# LINEARDriver_Amp.net
KiCad netlist of a schematic drawn in Altium Designer
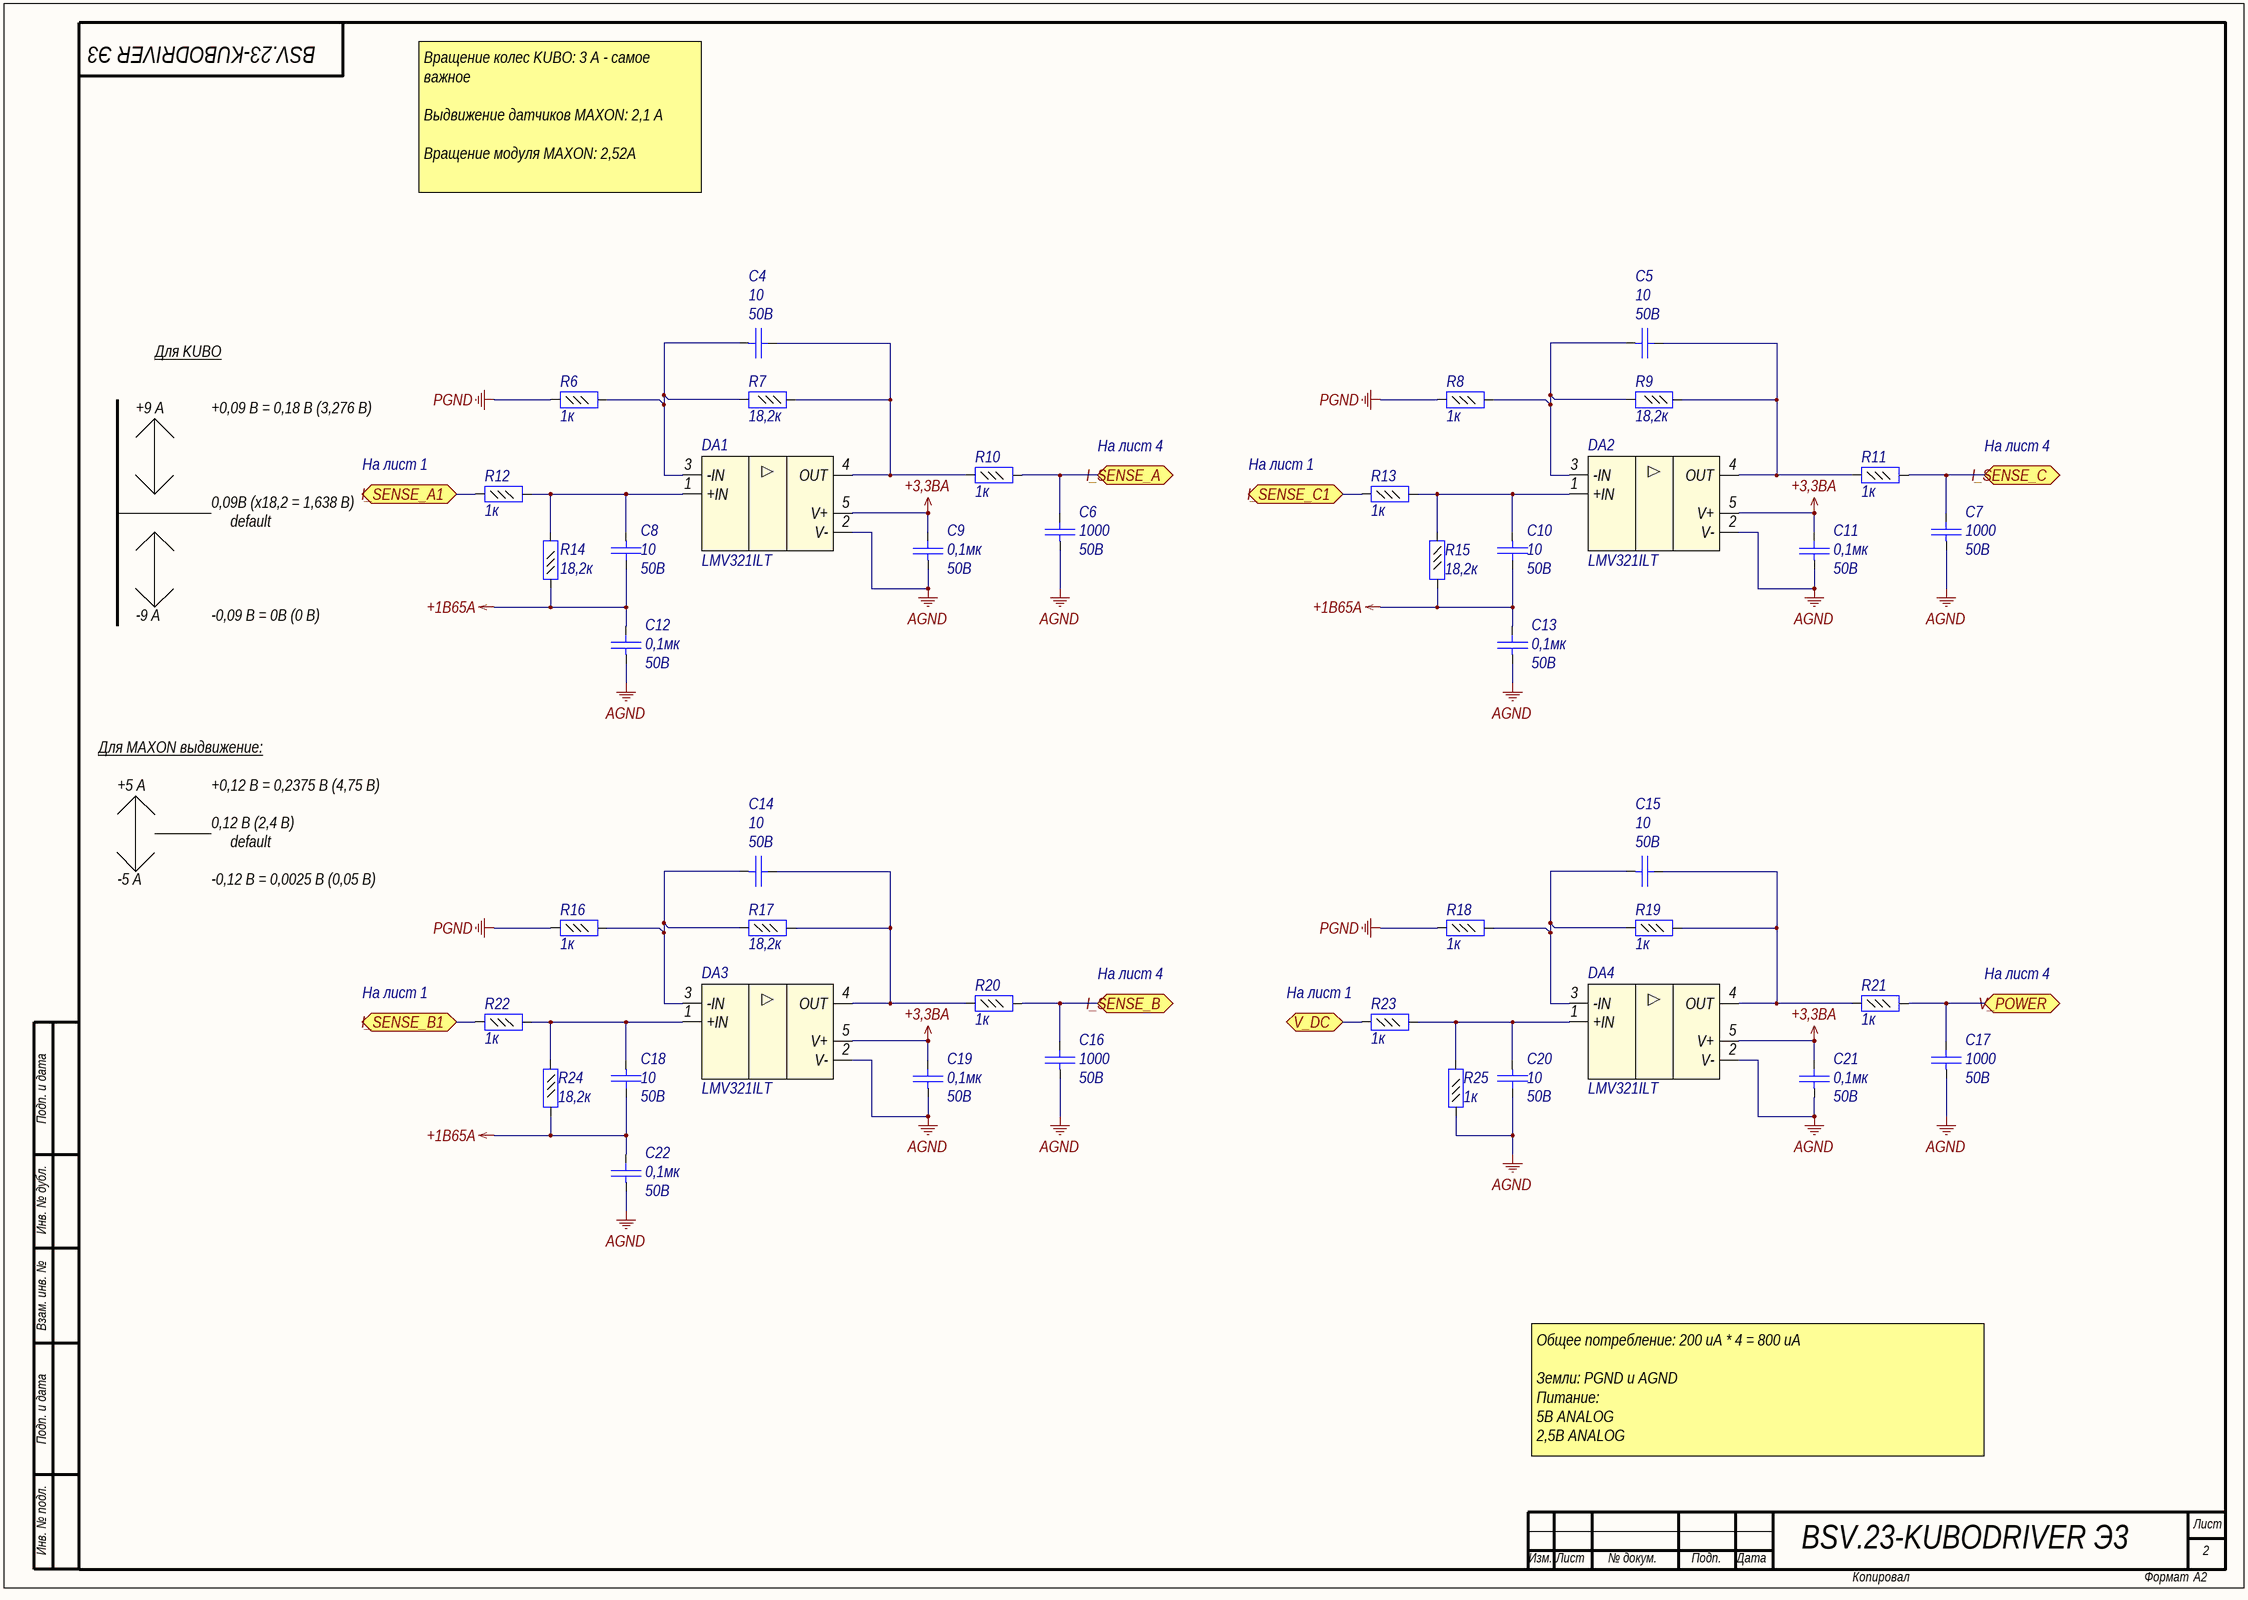
[diagram p0: LINEARDriver_Amp.SchDoc]

(export (version "E")
  (design (tool "Eeschema 10.0.6"))
  (components
    (comp (ref "C4")
      (value "10")
      (footprint "C0402")
      (description "Конденсатор")
      (fields
        (field (name "VOLTAGE") "50B")
        (field (name "PART NUMBER") "GRM1535C1H100J")
        (field (name "Comment") "Capacitor")
      )
      (libsource (lib "MOP44") (part "Capacitor"))
    )
    (comp (ref "C5")
      (value "10")
      (footprint "C0402")
      (description "Конденсатор")
      (fields
        (field (name "VOLTAGE") "50B")
        (field (name "PART NUMBER") "GRM1535C1H100J")
        (field (name "Comment") "Capacitor")
      )
      (libsource (lib "MOP44") (part "Capacitor"))
    )
    (comp (ref "C6")
      (value "1000")
      (footprint "C0402")
      (description "Конденсатор")
      (fields
        (field (name "VOLTAGE") "50B")
        (field (name "PART NUMBER") "GRM1555C1H102J")
        (field (name "Comment") "Capacitor")
      )
      (libsource (lib "MOP44") (part "Capacitor"))
    )
    (comp (ref "C7")
      (value "1000")
      (footprint "C0402")
      (description "Конденсатор")
      (fields
        (field (name "VOLTAGE") "50B")
        (field (name "PART NUMBER") "GRM1555C1H102J")
        (field (name "Comment") "Capacitor")
      )
      (libsource (lib "MOP44") (part "Capacitor"))
    )
    (comp (ref "C8")
      (value "10")
      (footprint "C0402")
      (description "Конденсатор")
      (fields
        (field (name "VOLTAGE") "50B")
        (field (name "PART NUMBER") "GRM1535C1H100J")
        (field (name "Comment") "Capacitor")
      )
      (libsource (lib "MOP44") (part "Capacitor"))
    )
    (comp (ref "C9")
      (value "0,1мк")
      (footprint "C0402")
      (description "Конденсатор")
      (fields
        (field (name "VOLTAGE") "50В")
        (field (name "PART NUMBER") "GRM155R71H104KE14D ")
        (field (name "Comment") "Capacitor")
      )
      (libsource (lib "MOP44") (part "Capacitor"))
    )
    (comp (ref "C10")
      (value "10")
      (footprint "C0402")
      (description "Конденсатор")
      (fields
        (field (name "VOLTAGE") "50B")
        (field (name "PART NUMBER") "GRM1535C1H100J")
        (field (name "Comment") "Capacitor")
      )
      (libsource (lib "MOP44") (part "Capacitor"))
    )
    (comp (ref "C11")
      (value "0,1мк")
      (footprint "C0402")
      (description "Конденсатор")
      (fields
        (field (name "VOLTAGE") "50В")
        (field (name "PART NUMBER") "GRM155R71H104KE14D ")
        (field (name "Comment") "Capacitor")
      )
      (libsource (lib "MOP44") (part "Capacitor"))
    )
    (comp (ref "C12")
      (value "0,1мк")
      (footprint "C0402")
      (description "Конденсатор")
      (fields
        (field (name "VOLTAGE") "50В")
        (field (name "PART NUMBER") "GRM155R71H104KE14D ")
        (field (name "Comment") "Capacitor")
      )
      (libsource (lib "MOP44") (part "Capacitor"))
    )
    (comp (ref "C13")
      (value "0,1мк")
      (footprint "C0402")
      (description "Конденсатор")
      (fields
        (field (name "VOLTAGE") "50В")
        (field (name "PART NUMBER") "GRM155R71H104KE14D ")
        (field (name "Comment") "Capacitor")
      )
      (libsource (lib "MOP44") (part "Capacitor"))
    )
    (comp (ref "C14")
      (value "10")
      (footprint "C0402")
      (description "Конденсатор")
      (fields
        (field (name "VOLTAGE") "50B")
        (field (name "PART NUMBER") "GRM1535C1H100J")
        (field (name "Comment") "Capacitor")
      )
      (libsource (lib "MOP44") (part "Capacitor"))
    )
    (comp (ref "C15")
      (value "10")
      (footprint "C0402")
      (description "Конденсатор")
      (fields
        (field (name "VOLTAGE") "50B")
        (field (name "PART NUMBER") "GRM1535C1H100J")
        (field (name "Comment") "Capacitor")
      )
      (libsource (lib "MOP44") (part "Capacitor"))
    )
    (comp (ref "C16")
      (value "1000")
      (footprint "C0402")
      (description "Конденсатор")
      (fields
        (field (name "VOLTAGE") "50B")
        (field (name "PART NUMBER") "GRM1555C1H102J")
        (field (name "Comment") "Capacitor")
      )
      (libsource (lib "MOP44") (part "Capacitor"))
    )
    (comp (ref "C17")
      (value "1000")
      (footprint "C0402")
      (description "Конденсатор")
      (fields
        (field (name "VOLTAGE") "50B")
        (field (name "PART NUMBER") "GRM1555C1H102J")
        (field (name "Comment") "Capacitor")
      )
      (libsource (lib "MOP44") (part "Capacitor"))
    )
    (comp (ref "C18")
      (value "10")
      (footprint "C0402")
      (description "Конденсатор")
      (fields
        (field (name "VOLTAGE") "50B")
        (field (name "PART NUMBER") "GRM1535C1H100J")
        (field (name "Comment") "Capacitor")
      )
      (libsource (lib "MOP44") (part "Capacitor"))
    )
    (comp (ref "C19")
      (value "0,1мк")
      (footprint "C0402")
      (description "Конденсатор")
      (fields
        (field (name "VOLTAGE") "50В")
        (field (name "PART NUMBER") "GRM155R71H104KE14D ")
        (field (name "Comment") "Capacitor")
      )
      (libsource (lib "MOP44") (part "Capacitor"))
    )
    (comp (ref "C20")
      (value "10")
      (footprint "C0402")
      (description "Конденсатор")
      (fields
        (field (name "VOLTAGE") "50B")
        (field (name "PART NUMBER") "GRM1535C1H100J")
        (field (name "Comment") "Capacitor")
      )
      (libsource (lib "MOP44") (part "Capacitor"))
    )
    (comp (ref "C21")
      (value "0,1мк")
      (footprint "C0402")
      (description "Конденсатор")
      (fields
        (field (name "VOLTAGE") "50В")
        (field (name "PART NUMBER") "GRM155R71H104KE14D ")
        (field (name "Comment") "Capacitor")
      )
      (libsource (lib "MOP44") (part "Capacitor"))
    )
    (comp (ref "C22")
      (value "0,1мк")
      (footprint "C0402")
      (description "Конденсатор")
      (fields
        (field (name "VOLTAGE") "50В")
        (field (name "PART NUMBER") "GRM155R71H104KE14D ")
        (field (name "Comment") "Capacitor")
      )
      (libsource (lib "MOP44") (part "Capacitor"))
    )
    (comp (ref "DA1")
      (value "LMV321ILT")
      (footprint "SOT23-5")
      (description "HIGH-DRIVE OPERATIONAL AMPLIFIERS WITH SHUTDOWN")
      (libsource (lib "MOP44") (part "LMV321ILT"))
    )
    (comp (ref "DA2")
      (value "LMV321ILT")
      (footprint "SOT23-5")
      (description "HIGH-DRIVE OPERATIONAL AMPLIFIERS WITH SHUTDOWN")
      (libsource (lib "MOP44") (part "LMV321ILT"))
    )
    (comp (ref "DA3")
      (value "LMV321ILT")
      (footprint "SOT23-5")
      (description "HIGH-DRIVE OPERATIONAL AMPLIFIERS WITH SHUTDOWN")
      (libsource (lib "MOP44") (part "LMV321ILT"))
    )
    (comp (ref "DA4")
      (value "LMV321ILT")
      (footprint "SOT23-5")
      (description "HIGH-DRIVE OPERATIONAL AMPLIFIERS WITH SHUTDOWN")
      (libsource (lib "MOP44") (part "LMV321ILT"))
    )
    (comp (ref "R6")
      (value "1к")
      (footprint "R0402")
      (description "Резистор")
      (fields (field (name "PART NUMBER") "RC0402FR-071KL") (field (name "POWER") "0,062Вт"))
      (libsource (lib "MOP44") (part "Resistor_0,062Вт"))
    )
    (comp (ref "R7")
      (value "18,2к")
      (footprint "R0402")
      (description "Резистор")
      (fields (field (name "PART NUMBER") "RC0402FR-0718K2L") (field (name "POWER") "0,062Вт"))
      (libsource (lib "") (part "Resistor_0,062Вт_2"))
    )
    (comp (ref "R8")
      (value "1к")
      (footprint "R0402")
      (description "Резистор")
      (fields (field (name "PART NUMBER") "RC0402FR-071KL") (field (name "POWER") "0,062Вт"))
      (libsource (lib "MOP44") (part "Resistor_0,062Вт"))
    )
    (comp (ref "R9")
      (value "18,2к")
      (footprint "R0402")
      (description "Резистор")
      (fields (field (name "PART NUMBER") "RC0402FR-0718K2L") (field (name "POWER") "0,062Вт"))
      (libsource (lib "") (part "Resistor_0,062Вт_2"))
    )
    (comp (ref "R10")
      (value "1к")
      (footprint "R0402")
      (description "Резистор")
      (fields (field (name "PART NUMBER") "RC0402FR-071KL") (field (name "POWER") "0,062Вт"))
      (libsource (lib "MOP44") (part "Resistor_0,062Вт"))
    )
    (comp (ref "R11")
      (value "1к")
      (footprint "R0402")
      (description "Резистор")
      (fields (field (name "PART NUMBER") "RC0402FR-071KL") (field (name "POWER") "0,062Вт"))
      (libsource (lib "MOP44") (part "Resistor_0,062Вт"))
    )
    (comp (ref "R12")
      (value "1к")
      (footprint "R0402")
      (description "Резистор")
      (fields (field (name "PART NUMBER") "RC0402FR-071KL") (field (name "POWER") "0,062Вт"))
      (libsource (lib "MOP44") (part "Resistor_0,062Вт"))
    )
    (comp (ref "R13")
      (value "1к")
      (footprint "R0402")
      (description "Резистор")
      (fields (field (name "PART NUMBER") "RC0402FR-071KL") (field (name "POWER") "0,062Вт"))
      (libsource (lib "MOP44") (part "Resistor_0,062Вт"))
    )
    (comp (ref "R14")
      (value "18,2к")
      (footprint "R0402")
      (description "Резистор")
      (fields (field (name "PART NUMBER") "RC0402FR-0718K2L") (field (name "POWER") "0,062Вт"))
      (libsource (lib "") (part "Resistor_0,062Вт_1"))
    )
    (comp (ref "R15")
      (value "18,2к")
      (footprint "R0402")
      (description "Резистор")
      (fields (field (name "PART NUMBER") "RC0402FR-0718K2L") (field (name "POWER") "0,062Вт"))
      (libsource (lib "") (part "Resistor_0,062Вт_3"))
    )
    (comp (ref "R16")
      (value "1к")
      (footprint "R0402")
      (description "Резистор")
      (fields (field (name "PART NUMBER") "RC0402FR-071KL") (field (name "POWER") "0,062Вт"))
      (libsource (lib "MOP44") (part "Resistor_0,062Вт"))
    )
    (comp (ref "R17")
      (value "18,2к")
      (footprint "R0402")
      (description "Резистор")
      (fields (field (name "PART NUMBER") "RC0402FR-0718K2L") (field (name "POWER") "0,062Вт"))
      (libsource (lib "MOP44") (part "Resistor_0,062Вт"))
    )
    (comp (ref "R18")
      (value "1к")
      (footprint "R0402")
      (description "Резистор")
      (fields (field (name "PART NUMBER") "RC0402FR-071KL") (field (name "POWER") "0,062Вт"))
      (libsource (lib "MOP44") (part "Resistor_0,062Вт"))
    )
    (comp (ref "R19")
      (value "1к")
      (footprint "R0402")
      (description "Резистор")
      (fields (field (name "PART NUMBER") "RC0402FR-071KL") (field (name "POWER") "0,062Вт"))
      (libsource (lib "MOP44") (part "Resistor_0,062Вт"))
    )
    (comp (ref "R20")
      (value "1к")
      (footprint "R0402")
      (description "Резистор")
      (fields (field (name "PART NUMBER") "RC0402FR-071KL") (field (name "POWER") "0,062Вт"))
      (libsource (lib "MOP44") (part "Resistor_0,062Вт"))
    )
    (comp (ref "R21")
      (value "1к")
      (footprint "R0402")
      (description "Резистор")
      (fields (field (name "PART NUMBER") "RC0402FR-071KL") (field (name "POWER") "0,062Вт"))
      (libsource (lib "MOP44") (part "Resistor_0,062Вт"))
    )
    (comp (ref "R22")
      (value "1к")
      (footprint "R0402")
      (description "Резистор")
      (fields (field (name "PART NUMBER") "RC0402FR-071KL") (field (name "POWER") "0,062Вт"))
      (libsource (lib "MOP44") (part "Resistor_0,062Вт"))
    )
    (comp (ref "R23")
      (value "1к")
      (footprint "R0402")
      (description "Резистор")
      (fields (field (name "PART NUMBER") "RC0402FR-071KL") (field (name "POWER") "0,062Вт"))
      (libsource (lib "MOP44") (part "Resistor_0,062Вт"))
    )
    (comp (ref "R24")
      (value "18,2к")
      (footprint "R0402")
      (description "Резистор")
      (fields (field (name "PART NUMBER") "RC0402FR-0718K2L") (field (name "POWER") "0,062Вт"))
      (libsource (lib "") (part "Resistor_0,062Вт_3"))
    )
    (comp (ref "R25")
      (value "1к")
      (footprint "R0402")
      (description "Резистор")
      (fields (field (name "PART NUMBER") "RC0402FR-071KL") (field (name "POWER") "0,062Вт"))
      (libsource (lib "") (part "Resistor_0,062Вт_1"))
    )
  )
  (nets
    (net (code "1") (name "+1B65A") (class "Default")
      (node (ref "C10") (pin "2") (pinfunction "2_2") (pintype "passive"))
      (node (ref "C12") (pin "2") (pinfunction "2_2") (pintype "passive"))
      (node (ref "C13") (pin "2") (pinfunction "2_2") (pintype "passive"))
      (node (ref "C18") (pin "2") (pinfunction "2_2") (pintype "passive"))
      (node (ref "C22") (pin "2") (pinfunction "2_2") (pintype "passive"))
      (node (ref "C8") (pin "2") (pinfunction "2_2") (pintype "passive"))
      (node (ref "R14") (pin "1") (pinfunction "1_1") (pintype "passive"))
      (node (ref "R15") (pin "2") (pinfunction "2_2") (pintype "passive"))
      (node (ref "R24") (pin "2") (pinfunction "2_2") (pintype "passive"))
    )
    (net (code "2") (name "+3,3BA") (class "Default")
      (node (ref "C11") (pin "2") (pinfunction "2_2") (pintype "passive"))
      (node (ref "C19") (pin "2") (pinfunction "2_2") (pintype "passive"))
      (node (ref "C21") (pin "2") (pinfunction "2_2") (pintype "passive"))
      (node (ref "C9") (pin "2") (pinfunction "2_2") (pintype "passive"))
      (node (ref "DA1") (pin "5") (pinfunction "V+_5") (pintype "passive"))
      (node (ref "DA2") (pin "5") (pinfunction "V+_5") (pintype "passive"))
      (node (ref "DA3") (pin "5") (pinfunction "V+_5") (pintype "passive"))
      (node (ref "DA4") (pin "5") (pinfunction "V+_5") (pintype "passive"))
    )
    (net (code "3") (name "/I_SENSE_A") (class "Default")
      (node (ref "C6") (pin "2") (pinfunction "2_2") (pintype "passive"))
      (node (ref "R10") (pin "2") (pinfunction "2_2") (pintype "passive"))
    )
    (net (code "4") (name "/I_SENSE_A1") (class "Default")
      (node (ref "R12") (pin "1") (pinfunction "1_1") (pintype "passive"))
    )
    (net (code "5") (name "/I_SENSE_B") (class "Default")
      (node (ref "C16") (pin "2") (pinfunction "2_2") (pintype "passive"))
      (node (ref "R20") (pin "2") (pinfunction "2_2") (pintype "passive"))
    )
    (net (code "6") (name "/I_SENSE_B1") (class "Default")
      (node (ref "R22") (pin "1") (pinfunction "1_1") (pintype "passive"))
    )
    (net (code "7") (name "/I_SENSE_C") (class "Default")
      (node (ref "C7") (pin "2") (pinfunction "2_2") (pintype "passive"))
      (node (ref "R11") (pin "2") (pinfunction "2_2") (pintype "passive"))
    )
    (net (code "8") (name "/I_SENSE_C1") (class "Default")
      (node (ref "R13") (pin "1") (pinfunction "1_1") (pintype "passive"))
    )
    (net (code "9") (name "/V_DC") (class "Default")
      (node (ref "R23") (pin "1") (pinfunction "1_1") (pintype "passive"))
    )
    (net (code "10") (name "/V_POWER") (class "Default")
      (node (ref "C17") (pin "2") (pinfunction "2_2") (pintype "passive"))
      (node (ref "R21") (pin "2") (pinfunction "2_2") (pintype "passive"))
    )
    (net (code "11") (name "AGND") (class "Default")
      (node (ref "C11") (pin "1") (pinfunction "1_1") (pintype "passive"))
      (node (ref "C12") (pin "1") (pinfunction "1_1") (pintype "passive"))
      (node (ref "C13") (pin "1") (pinfunction "1_1") (pintype "passive"))
      (node (ref "C16") (pin "1") (pinfunction "1_1") (pintype "passive"))
      (node (ref "C17") (pin "1") (pinfunction "1_1") (pintype "passive"))
      (node (ref "C19") (pin "1") (pinfunction "1_1") (pintype "passive"))
      (node (ref "C20") (pin "2") (pinfunction "2_2") (pintype "passive"))
      (node (ref "C21") (pin "1") (pinfunction "1_1") (pintype "passive"))
      (node (ref "C22") (pin "1") (pinfunction "1_1") (pintype "passive"))
      (node (ref "C6") (pin "1") (pinfunction "1_1") (pintype "passive"))
      (node (ref "C7") (pin "1") (pinfunction "1_1") (pintype "passive"))
      (node (ref "C9") (pin "1") (pinfunction "1_1") (pintype "passive"))
      (node (ref "DA1") (pin "2") (pinfunction "V-_2") (pintype "passive"))
      (node (ref "DA2") (pin "2") (pinfunction "V-_2") (pintype "passive"))
      (node (ref "DA3") (pin "2") (pinfunction "V-_2") (pintype "passive"))
      (node (ref "DA4") (pin "2") (pinfunction "V-_2") (pintype "passive"))
      (node (ref "R25") (pin "1") (pinfunction "1_1") (pintype "passive"))
    )
    (net (code "12") (name "Net-(DA1-+IN)") (class "Default")
      (node (ref "C8") (pin "1") (pinfunction "1_1") (pintype "passive"))
      (node (ref "DA1") (pin "1") (pinfunction "+IN_1") (pintype "passive"))
      (node (ref "R12") (pin "2") (pinfunction "2_2") (pintype "passive"))
      (node (ref "R14") (pin "2") (pinfunction "2_2") (pintype "passive"))
    )
    (net (code "13") (name "Net-(DA1--IN)") (class "Default")
      (node (ref "C4") (pin "1") (pinfunction "1_1") (pintype "passive"))
      (node (ref "DA1") (pin "3") (pinfunction "-IN_3") (pintype "passive"))
      (node (ref "R6") (pin "2") (pinfunction "2_2") (pintype "passive"))
      (node (ref "R7") (pin "2") (pinfunction "2_2") (pintype "passive"))
    )
    (net (code "14") (name "Net-(DA1-OUT)") (class "Default")
      (node (ref "C4") (pin "2") (pinfunction "2_2") (pintype "passive"))
      (node (ref "DA1") (pin "4") (pinfunction "OUT_4") (pintype "passive"))
      (node (ref "R10") (pin "1") (pinfunction "1_1") (pintype "passive"))
      (node (ref "R7") (pin "1") (pinfunction "1_1") (pintype "passive"))
    )
    (net (code "15") (name "Net-(DA2-+IN)") (class "Default")
      (node (ref "C10") (pin "1") (pinfunction "1_1") (pintype "passive"))
      (node (ref "DA2") (pin "1") (pinfunction "+IN_1") (pintype "passive"))
      (node (ref "R13") (pin "2") (pinfunction "2_2") (pintype "passive"))
      (node (ref "R15") (pin "1") (pinfunction "1_1") (pintype "passive"))
    )
    (net (code "16") (name "Net-(DA2--IN)") (class "Default")
      (node (ref "C5") (pin "1") (pinfunction "1_1") (pintype "passive"))
      (node (ref "DA2") (pin "3") (pinfunction "-IN_3") (pintype "passive"))
      (node (ref "R8") (pin "2") (pinfunction "2_2") (pintype "passive"))
      (node (ref "R9") (pin "2") (pinfunction "2_2") (pintype "passive"))
    )
    (net (code "17") (name "Net-(DA2-OUT)") (class "Default")
      (node (ref "C5") (pin "2") (pinfunction "2_2") (pintype "passive"))
      (node (ref "DA2") (pin "4") (pinfunction "OUT_4") (pintype "passive"))
      (node (ref "R11") (pin "1") (pinfunction "1_1") (pintype "passive"))
      (node (ref "R9") (pin "1") (pinfunction "1_1") (pintype "passive"))
    )
    (net (code "18") (name "Net-(DA3-+IN)") (class "Default")
      (node (ref "C18") (pin "1") (pinfunction "1_1") (pintype "passive"))
      (node (ref "DA3") (pin "1") (pinfunction "+IN_1") (pintype "passive"))
      (node (ref "R22") (pin "2") (pinfunction "2_2") (pintype "passive"))
      (node (ref "R24") (pin "1") (pinfunction "1_1") (pintype "passive"))
    )
    (net (code "19") (name "Net-(DA3--IN)") (class "Default")
      (node (ref "C14") (pin "1") (pinfunction "1_1") (pintype "passive"))
      (node (ref "DA3") (pin "3") (pinfunction "-IN_3") (pintype "passive"))
      (node (ref "R16") (pin "2") (pinfunction "2_2") (pintype "passive"))
      (node (ref "R17") (pin "1") (pinfunction "1_1") (pintype "passive"))
    )
    (net (code "20") (name "Net-(DA3-OUT)") (class "Default")
      (node (ref "C14") (pin "2") (pinfunction "2_2") (pintype "passive"))
      (node (ref "DA3") (pin "4") (pinfunction "OUT_4") (pintype "passive"))
      (node (ref "R17") (pin "2") (pinfunction "2_2") (pintype "passive"))
      (node (ref "R20") (pin "1") (pinfunction "1_1") (pintype "passive"))
    )
    (net (code "21") (name "Net-(DA4-+IN)") (class "Default")
      (node (ref "C20") (pin "1") (pinfunction "1_1") (pintype "passive"))
      (node (ref "DA4") (pin "1") (pinfunction "+IN_1") (pintype "passive"))
      (node (ref "R23") (pin "2") (pinfunction "2_2") (pintype "passive"))
      (node (ref "R25") (pin "2") (pinfunction "2_2") (pintype "passive"))
    )
    (net (code "22") (name "Net-(DA4--IN)") (class "Default")
      (node (ref "C15") (pin "1") (pinfunction "1_1") (pintype "passive"))
      (node (ref "DA4") (pin "3") (pinfunction "-IN_3") (pintype "passive"))
      (node (ref "R18") (pin "2") (pinfunction "2_2") (pintype "passive"))
      (node (ref "R19") (pin "1") (pinfunction "1_1") (pintype "passive"))
    )
    (net (code "23") (name "Net-(DA4-OUT)") (class "Default")
      (node (ref "C15") (pin "2") (pinfunction "2_2") (pintype "passive"))
      (node (ref "DA4") (pin "4") (pinfunction "OUT_4") (pintype "passive"))
      (node (ref "R19") (pin "2") (pinfunction "2_2") (pintype "passive"))
      (node (ref "R21") (pin "1") (pinfunction "1_1") (pintype "passive"))
    )
    (net (code "24") (name "PGND") (class "Default")
      (node (ref "R16") (pin "1") (pinfunction "1_1") (pintype "passive"))
      (node (ref "R18") (pin "1") (pinfunction "1_1") (pintype "passive"))
      (node (ref "R6") (pin "1") (pinfunction "1_1") (pintype "passive"))
      (node (ref "R8") (pin "1") (pinfunction "1_1") (pintype "passive"))
    )
  )
)
